# th-566-vco-io.net
KiCad netlist of a schematic drawn in EAGLE
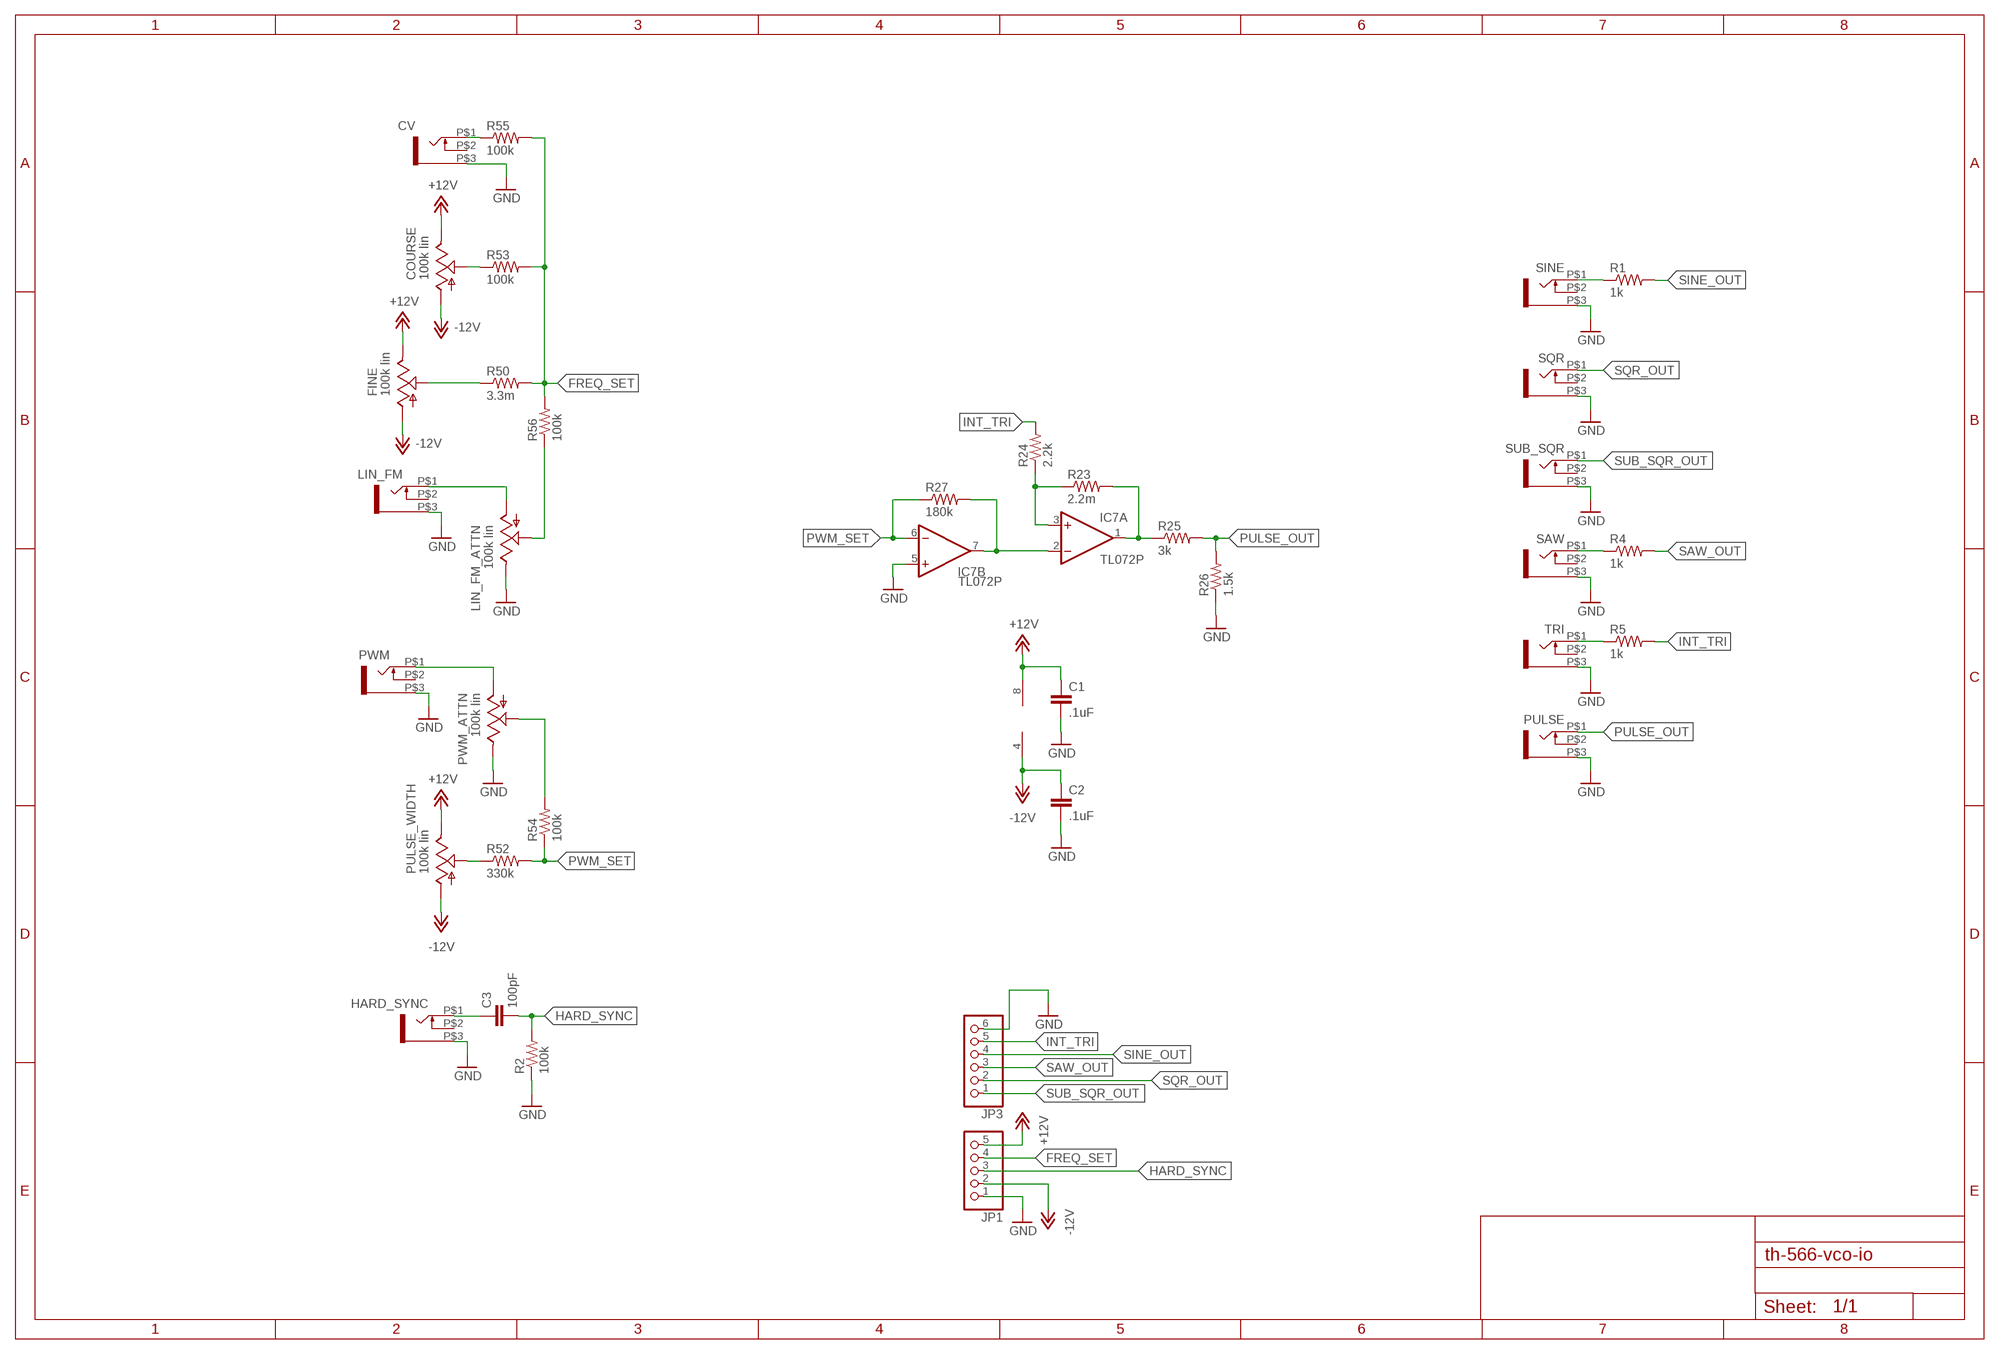
[diagram p0: schematic, sheet 1]

(export (version "E")
  (design (tool "Eeschema 10.0.6"))
  (components
    (comp (ref "C1")
      (value ".1uF")
      (footprint "eagle-import:C050-024X044")
      (libsource (lib "eagle-import") (part "C-EU050-024X044"))
    )
    (comp (ref "C2")
      (value ".1uF")
      (footprint "eagle-import:C050-024X044")
      (libsource (lib "eagle-import") (part "C-EU050-024X044"))
    )
    (comp (ref "C3")
      (value "100pF")
      (footprint "eagle-import:C050-024X044")
      (libsource (lib "eagle-import") (part "C-EU050-024X044"))
    )
    (comp (ref "COURSE")
      (value "100k lin")
      (footprint "eagle-import:EVUF")
      (libsource (lib "eagle-import") (part "ALPHA-9MMA"))
    )
    (comp (ref "CV")
      (value "WQP-PJ301M-12_JACK")
      (footprint "eagle-import:WQP-PJ301M-12_JACK")
      (libsource (lib "eagle-import") (part "WQP-PJ301M-12_JACK"))
    )
    (comp (ref "FINE")
      (value "100k lin")
      (footprint "eagle-import:EVUF")
      (libsource (lib "eagle-import") (part "ALPHA-9MMA"))
    )
    (comp (ref "HARD_SYNC")
      (value "WQP-PJ301M-12_JACK")
      (footprint "eagle-import:WQP-PJ301M-12_JACK")
      (libsource (lib "eagle-import") (part "WQP-PJ301M-12_JACK"))
    )
    (comp (ref "IC7")
      (value "TL072P")
      (footprint "eagle-import:DIL08")
      (libsource (lib "eagle-import") (part "TL072P"))
    )
    (comp (ref "JP1")
      (value "PINHD-1X5")
      (footprint "eagle-import:1X05")
      (libsource (lib "eagle-import") (part "PINHD-1X5"))
    )
    (comp (ref "JP3")
      (value "PINHD-1X6")
      (footprint "eagle-import:1X06")
      (libsource (lib "eagle-import") (part "PINHD-1X6"))
    )
    (comp (ref "LIN_FM")
      (value "WQP-PJ301M-12_JACK")
      (footprint "eagle-import:WQP-PJ301M-12_JACK")
      (libsource (lib "eagle-import") (part "WQP-PJ301M-12_JACK"))
    )
    (comp (ref "LIN_FM_ATTN")
      (value "100k lin")
      (footprint "eagle-import:EVUF")
      (libsource (lib "eagle-import") (part "ALPHA-9MMA"))
    )
    (comp (ref "PULSE")
      (value "WQP-PJ301M-12_JACK")
      (footprint "eagle-import:WQP-PJ301M-12_JACK")
      (libsource (lib "eagle-import") (part "WQP-PJ301M-12_JACK"))
    )
    (comp (ref "PULSE_WIDTH")
      (value "100k lin")
      (footprint "eagle-import:EVUF")
      (libsource (lib "eagle-import") (part "ALPHA-9MMA"))
    )
    (comp (ref "PWM")
      (value "WQP-PJ301M-12_JACK")
      (footprint "eagle-import:WQP-PJ301M-12_JACK")
      (libsource (lib "eagle-import") (part "WQP-PJ301M-12_JACK"))
    )
    (comp (ref "PWM_ATTN")
      (value "100k lin")
      (footprint "eagle-import:EVUF")
      (libsource (lib "eagle-import") (part "ALPHA-9MMA"))
    )
    (comp (ref "R1")
      (value "1k")
      (footprint "eagle-import:0204_7")
      (libsource (lib "eagle-import") (part "R-US_0204/7"))
    )
    (comp (ref "R2")
      (value "100k")
      (footprint "eagle-import:0204_7")
      (libsource (lib "eagle-import") (part "R-US_0204/7"))
    )
    (comp (ref "R4")
      (value "1k")
      (footprint "eagle-import:0204_7")
      (libsource (lib "eagle-import") (part "R-US_0204/7"))
    )
    (comp (ref "R5")
      (value "1k")
      (footprint "eagle-import:0204_7")
      (libsource (lib "eagle-import") (part "R-US_0204/7"))
    )
    (comp (ref "R23")
      (value "2.2m")
      (footprint "eagle-import:0204_7")
      (libsource (lib "eagle-import") (part "R-US_0204/7"))
    )
    (comp (ref "R24")
      (value "2.2k")
      (footprint "eagle-import:0204_7")
      (libsource (lib "eagle-import") (part "R-US_0204/7"))
    )
    (comp (ref "R25")
      (value "3k")
      (footprint "eagle-import:0204_7")
      (libsource (lib "eagle-import") (part "R-US_0204/7"))
    )
    (comp (ref "R26")
      (value "1.5k")
      (footprint "eagle-import:0204_7")
      (libsource (lib "eagle-import") (part "R-US_0204/7"))
    )
    (comp (ref "R27")
      (value "180k")
      (footprint "eagle-import:0204_7")
      (libsource (lib "eagle-import") (part "R-US_0204/7"))
    )
    (comp (ref "R50")
      (value "3.3m")
      (footprint "eagle-import:0204_7")
      (libsource (lib "eagle-import") (part "R-US_0204/7"))
    )
    (comp (ref "R52")
      (value "330k")
      (footprint "eagle-import:0204_7")
      (libsource (lib "eagle-import") (part "R-US_0204/7"))
    )
    (comp (ref "R53")
      (value "100k")
      (footprint "eagle-import:0204_7")
      (libsource (lib "eagle-import") (part "R-US_0204/7"))
    )
    (comp (ref "R54")
      (value "100k")
      (footprint "eagle-import:0204_7")
      (libsource (lib "eagle-import") (part "R-US_0204/7"))
    )
    (comp (ref "R55")
      (value "100k")
      (footprint "eagle-import:0204_7")
      (libsource (lib "eagle-import") (part "R-US_0204/7"))
    )
    (comp (ref "R56")
      (value "100k")
      (footprint "eagle-import:0204_7")
      (libsource (lib "eagle-import") (part "R-US_0204/7"))
    )
    (comp (ref "SAW")
      (value "WQP-PJ301M-12_JACK")
      (footprint "eagle-import:WQP-PJ301M-12_JACK")
      (libsource (lib "eagle-import") (part "WQP-PJ301M-12_JACK"))
    )
    (comp (ref "SINE")
      (value "WQP-PJ301M-12_JACK")
      (footprint "eagle-import:WQP-PJ301M-12_JACK")
      (libsource (lib "eagle-import") (part "WQP-PJ301M-12_JACK"))
    )
    (comp (ref "SQR")
      (value "WQP-PJ301M-12_JACK")
      (footprint "eagle-import:WQP-PJ301M-12_JACK")
      (libsource (lib "eagle-import") (part "WQP-PJ301M-12_JACK"))
    )
    (comp (ref "SUB_SQR")
      (value "WQP-PJ301M-12_JACK")
      (footprint "eagle-import:WQP-PJ301M-12_JACK")
      (libsource (lib "eagle-import") (part "WQP-PJ301M-12_JACK"))
    )
    (comp (ref "TRI")
      (value "WQP-PJ301M-12_JACK")
      (footprint "eagle-import:WQP-PJ301M-12_JACK")
      (libsource (lib "eagle-import") (part "WQP-PJ301M-12_JACK"))
    )
  )
  (nets
    (net (code "1") (name "+12V") (class "Default")
      (node (ref "C1") (pin "1") (pinfunction "1_1") (pintype "passive"))
      (node (ref "COURSE") (pin "3") (pinfunction "E_3") (pintype "passive"))
      (node (ref "FINE") (pin "3") (pinfunction "E_3") (pintype "passive"))
      (node (ref "IC7") (pin "8") (pinfunction "V+_8") (pintype "power_in"))
      (node (ref "JP1") (pin "5") (pinfunction "5_5") (pintype "passive"))
      (node (ref "PULSE_WIDTH") (pin "3") (pinfunction "E_3") (pintype "passive"))
    )
    (net (code "2") (name "-12V") (class "Default")
      (node (ref "C2") (pin "1") (pinfunction "1_1") (pintype "passive"))
      (node (ref "COURSE") (pin "1") (pinfunction "A_1") (pintype "passive"))
      (node (ref "FINE") (pin "1") (pinfunction "A_1") (pintype "passive"))
      (node (ref "IC7") (pin "4") (pinfunction "V-_4") (pintype "power_in"))
      (node (ref "JP1") (pin "2") (pinfunction "2_2") (pintype "passive"))
      (node (ref "PULSE_WIDTH") (pin "1") (pinfunction "A_1") (pintype "passive"))
    )
    (net (code "3") (name "FREQ_SET") (class "Default")
      (node (ref "JP1") (pin "4") (pinfunction "4_4") (pintype "passive"))
      (node (ref "R50") (pin "2") (pinfunction "2_2") (pintype "passive"))
      (node (ref "R53") (pin "2") (pinfunction "2_2") (pintype "passive"))
      (node (ref "R55") (pin "2") (pinfunction "2_2") (pintype "passive"))
      (node (ref "R56") (pin "2") (pinfunction "2_2") (pintype "passive"))
    )
    (net (code "4") (name "GND") (class "Default")
      (node (ref "C1") (pin "2") (pinfunction "2_2") (pintype "passive"))
      (node (ref "C2") (pin "2") (pinfunction "2_2") (pintype "passive"))
      (node (ref "CV") (pin "P$3") (pinfunction "1_P$3") (pintype "passive"))
      (node (ref "HARD_SYNC") (pin "P$3") (pinfunction "1_P$3") (pintype "passive"))
      (node (ref "IC7") (pin "5") (pinfunction "+IN_5") (pintype "input"))
      (node (ref "JP1") (pin "1") (pinfunction "1_1") (pintype "passive"))
      (node (ref "JP3") (pin "6") (pinfunction "6_6") (pintype "passive"))
      (node (ref "LIN_FM") (pin "P$3") (pinfunction "1_P$3") (pintype "passive"))
      (node (ref "LIN_FM_ATTN") (pin "3") (pinfunction "E_3") (pintype "passive"))
      (node (ref "PULSE") (pin "P$3") (pinfunction "1_P$3") (pintype "passive"))
      (node (ref "PWM") (pin "P$3") (pinfunction "1_P$3") (pintype "passive"))
      (node (ref "PWM_ATTN") (pin "3") (pinfunction "E_3") (pintype "passive"))
      (node (ref "R2") (pin "1") (pinfunction "1_1") (pintype "passive"))
      (node (ref "R26") (pin "1") (pinfunction "1_1") (pintype "passive"))
      (node (ref "SAW") (pin "P$3") (pinfunction "1_P$3") (pintype "passive"))
      (node (ref "SINE") (pin "P$3") (pinfunction "1_P$3") (pintype "passive"))
      (node (ref "SQR") (pin "P$3") (pinfunction "1_P$3") (pintype "passive"))
      (node (ref "SUB_SQR") (pin "P$3") (pinfunction "1_P$3") (pintype "passive"))
      (node (ref "TRI") (pin "P$3") (pinfunction "1_P$3") (pintype "passive"))
    )
    (net (code "5") (name "HARD_SYNC") (class "Default")
      (node (ref "C3") (pin "2") (pinfunction "2_2") (pintype "passive"))
      (node (ref "JP1") (pin "3") (pinfunction "3_3") (pintype "passive"))
      (node (ref "R2") (pin "2") (pinfunction "2_2") (pintype "passive"))
    )
    (net (code "6") (name "INT_TRI") (class "Default")
      (node (ref "JP3") (pin "5") (pinfunction "5_5") (pintype "passive"))
      (node (ref "R24") (pin "2") (pinfunction "2_2") (pintype "passive"))
      (node (ref "R5") (pin "2") (pinfunction "2_2") (pintype "passive"))
    )
    (net (code "7") (name "Net-(COURSE-S)") (class "Default")
      (node (ref "COURSE") (pin "2") (pinfunction "S_2") (pintype "passive"))
      (node (ref "R53") (pin "1") (pinfunction "1_1") (pintype "passive"))
    )
    (net (code "8") (name "Net-(CV-2)") (class "Default")
      (node (ref "CV") (pin "P$1") (pinfunction "2_P$1") (pintype "passive"))
      (node (ref "R55") (pin "1") (pinfunction "1_1") (pintype "passive"))
    )
    (net (code "9") (name "Net-(FINE-S)") (class "Default")
      (node (ref "FINE") (pin "2") (pinfunction "S_2") (pintype "passive"))
      (node (ref "R50") (pin "1") (pinfunction "1_1") (pintype "passive"))
    )
    (net (code "10") (name "Net-(HARD_SYNC-2)") (class "Default")
      (node (ref "C3") (pin "1") (pinfunction "1_1") (pintype "passive"))
      (node (ref "HARD_SYNC") (pin "P$1") (pinfunction "2_P$1") (pintype "passive"))
    )
    (net (code "11") (name "Net-(IC7A-+IN)") (class "Default")
      (node (ref "IC7") (pin "3") (pinfunction "+IN_3") (pintype "input"))
      (node (ref "R23") (pin "1") (pinfunction "1_1") (pintype "passive"))
      (node (ref "R24") (pin "1") (pinfunction "1_1") (pintype "passive"))
    )
    (net (code "12") (name "Net-(IC7A--IN)") (class "Default")
      (node (ref "IC7") (pin "2") (pinfunction "-IN_2") (pintype "input"))
      (node (ref "IC7") (pin "7") (pinfunction "OUT_7") (pintype "output"))
      (node (ref "R27") (pin "2") (pinfunction "2_2") (pintype "passive"))
    )
    (net (code "13") (name "Net-(IC7A-OUT)") (class "Default")
      (node (ref "IC7") (pin "1") (pinfunction "OUT_1") (pintype "output"))
      (node (ref "R23") (pin "2") (pinfunction "2_2") (pintype "passive"))
      (node (ref "R25") (pin "1") (pinfunction "1_1") (pintype "passive"))
    )
    (net (code "14") (name "Net-(LIN_FM-2)") (class "Default")
      (node (ref "LIN_FM") (pin "P$1") (pinfunction "2_P$1") (pintype "passive"))
      (node (ref "LIN_FM_ATTN") (pin "1") (pinfunction "A_1") (pintype "passive"))
    )
    (net (code "15") (name "Net-(LIN_FM_ATTN-S)") (class "Default")
      (node (ref "LIN_FM_ATTN") (pin "2") (pinfunction "S_2") (pintype "passive"))
      (node (ref "R56") (pin "1") (pinfunction "1_1") (pintype "passive"))
    )
    (net (code "16") (name "Net-(PULSE_WIDTH-S)") (class "Default")
      (node (ref "PULSE_WIDTH") (pin "2") (pinfunction "S_2") (pintype "passive"))
      (node (ref "R52") (pin "1") (pinfunction "1_1") (pintype "passive"))
    )
    (net (code "17") (name "Net-(PWM-2)") (class "Default")
      (node (ref "PWM") (pin "P$1") (pinfunction "2_P$1") (pintype "passive"))
      (node (ref "PWM_ATTN") (pin "1") (pinfunction "A_1") (pintype "passive"))
    )
    (net (code "18") (name "Net-(PWM_ATTN-S)") (class "Default")
      (node (ref "PWM_ATTN") (pin "2") (pinfunction "S_2") (pintype "passive"))
      (node (ref "R54") (pin "2") (pinfunction "2_2") (pintype "passive"))
    )
    (net (code "19") (name "Net-(SAW-2)") (class "Default")
      (node (ref "R4") (pin "1") (pinfunction "1_1") (pintype "passive"))
      (node (ref "SAW") (pin "P$1") (pinfunction "2_P$1") (pintype "passive"))
    )
    (net (code "20") (name "Net-(SINE-2)") (class "Default")
      (node (ref "R1") (pin "1") (pinfunction "1_1") (pintype "passive"))
      (node (ref "SINE") (pin "P$1") (pinfunction "2_P$1") (pintype "passive"))
    )
    (net (code "21") (name "Net-(TRI-2)") (class "Default")
      (node (ref "R5") (pin "1") (pinfunction "1_1") (pintype "passive"))
      (node (ref "TRI") (pin "P$1") (pinfunction "2_P$1") (pintype "passive"))
    )
    (net (code "22") (name "PULSE_OUT") (class "Default")
      (node (ref "PULSE") (pin "P$1") (pinfunction "2_P$1") (pintype "passive"))
      (node (ref "R25") (pin "2") (pinfunction "2_2") (pintype "passive"))
      (node (ref "R26") (pin "2") (pinfunction "2_2") (pintype "passive"))
    )
    (net (code "23") (name "PWM_SET") (class "Default")
      (node (ref "IC7") (pin "6") (pinfunction "-IN_6") (pintype "input"))
      (node (ref "R27") (pin "1") (pinfunction "1_1") (pintype "passive"))
      (node (ref "R52") (pin "2") (pinfunction "2_2") (pintype "passive"))
      (node (ref "R54") (pin "1") (pinfunction "1_1") (pintype "passive"))
    )
    (net (code "24") (name "SAW_OUT") (class "Default")
      (node (ref "JP3") (pin "3") (pinfunction "3_3") (pintype "passive"))
      (node (ref "R4") (pin "2") (pinfunction "2_2") (pintype "passive"))
    )
    (net (code "25") (name "SINE_OUT") (class "Default")
      (node (ref "JP3") (pin "4") (pinfunction "4_4") (pintype "passive"))
      (node (ref "R1") (pin "2") (pinfunction "2_2") (pintype "passive"))
    )
    (net (code "26") (name "SQR_OUT") (class "Default")
      (node (ref "JP3") (pin "2") (pinfunction "2_2") (pintype "passive"))
      (node (ref "SQR") (pin "P$1") (pinfunction "2_P$1") (pintype "passive"))
    )
    (net (code "27") (name "SUB_SQR_OUT") (class "Default")
      (node (ref "JP3") (pin "1") (pinfunction "1_1") (pintype "passive"))
      (node (ref "SUB_SQR") (pin "P$1") (pinfunction "2_P$1") (pintype "passive"))
    )
    (net (code "28") (name "unconnected-(CV-3-PadP$2)") (class "Default")
      (node (ref "CV") (pin "P$2") (pinfunction "3_P$2") (pintype "passive"))
    )
    (net (code "29") (name "unconnected-(HARD_SYNC-3-PadP$2)") (class "Default")
      (node (ref "HARD_SYNC") (pin "P$2") (pinfunction "3_P$2") (pintype "passive"))
    )
    (net (code "30") (name "unconnected-(LIN_FM-3-PadP$2)") (class "Default")
      (node (ref "LIN_FM") (pin "P$2") (pinfunction "3_P$2") (pintype "passive"))
    )
    (net (code "31") (name "unconnected-(PULSE-3-PadP$2)") (class "Default")
      (node (ref "PULSE") (pin "P$2") (pinfunction "3_P$2") (pintype "passive"))
    )
    (net (code "32") (name "unconnected-(PWM-3-PadP$2)") (class "Default")
      (node (ref "PWM") (pin "P$2") (pinfunction "3_P$2") (pintype "passive"))
    )
    (net (code "33") (name "unconnected-(SAW-3-PadP$2)") (class "Default")
      (node (ref "SAW") (pin "P$2") (pinfunction "3_P$2") (pintype "passive"))
    )
    (net (code "34") (name "unconnected-(SINE-3-PadP$2)") (class "Default")
      (node (ref "SINE") (pin "P$2") (pinfunction "3_P$2") (pintype "passive"))
    )
    (net (code "35") (name "unconnected-(SQR-3-PadP$2)") (class "Default")
      (node (ref "SQR") (pin "P$2") (pinfunction "3_P$2") (pintype "passive"))
    )
    (net (code "36") (name "unconnected-(SUB_SQR-3-PadP$2)") (class "Default")
      (node (ref "SUB_SQR") (pin "P$2") (pinfunction "3_P$2") (pintype "passive"))
    )
    (net (code "37") (name "unconnected-(TRI-3-PadP$2)") (class "Default")
      (node (ref "TRI") (pin "P$2") (pinfunction "3_P$2") (pintype "passive"))
    )
  )
)
